# pc_openpressure_basic.net
KiCad netlist of a schematic drawn in EAGLE
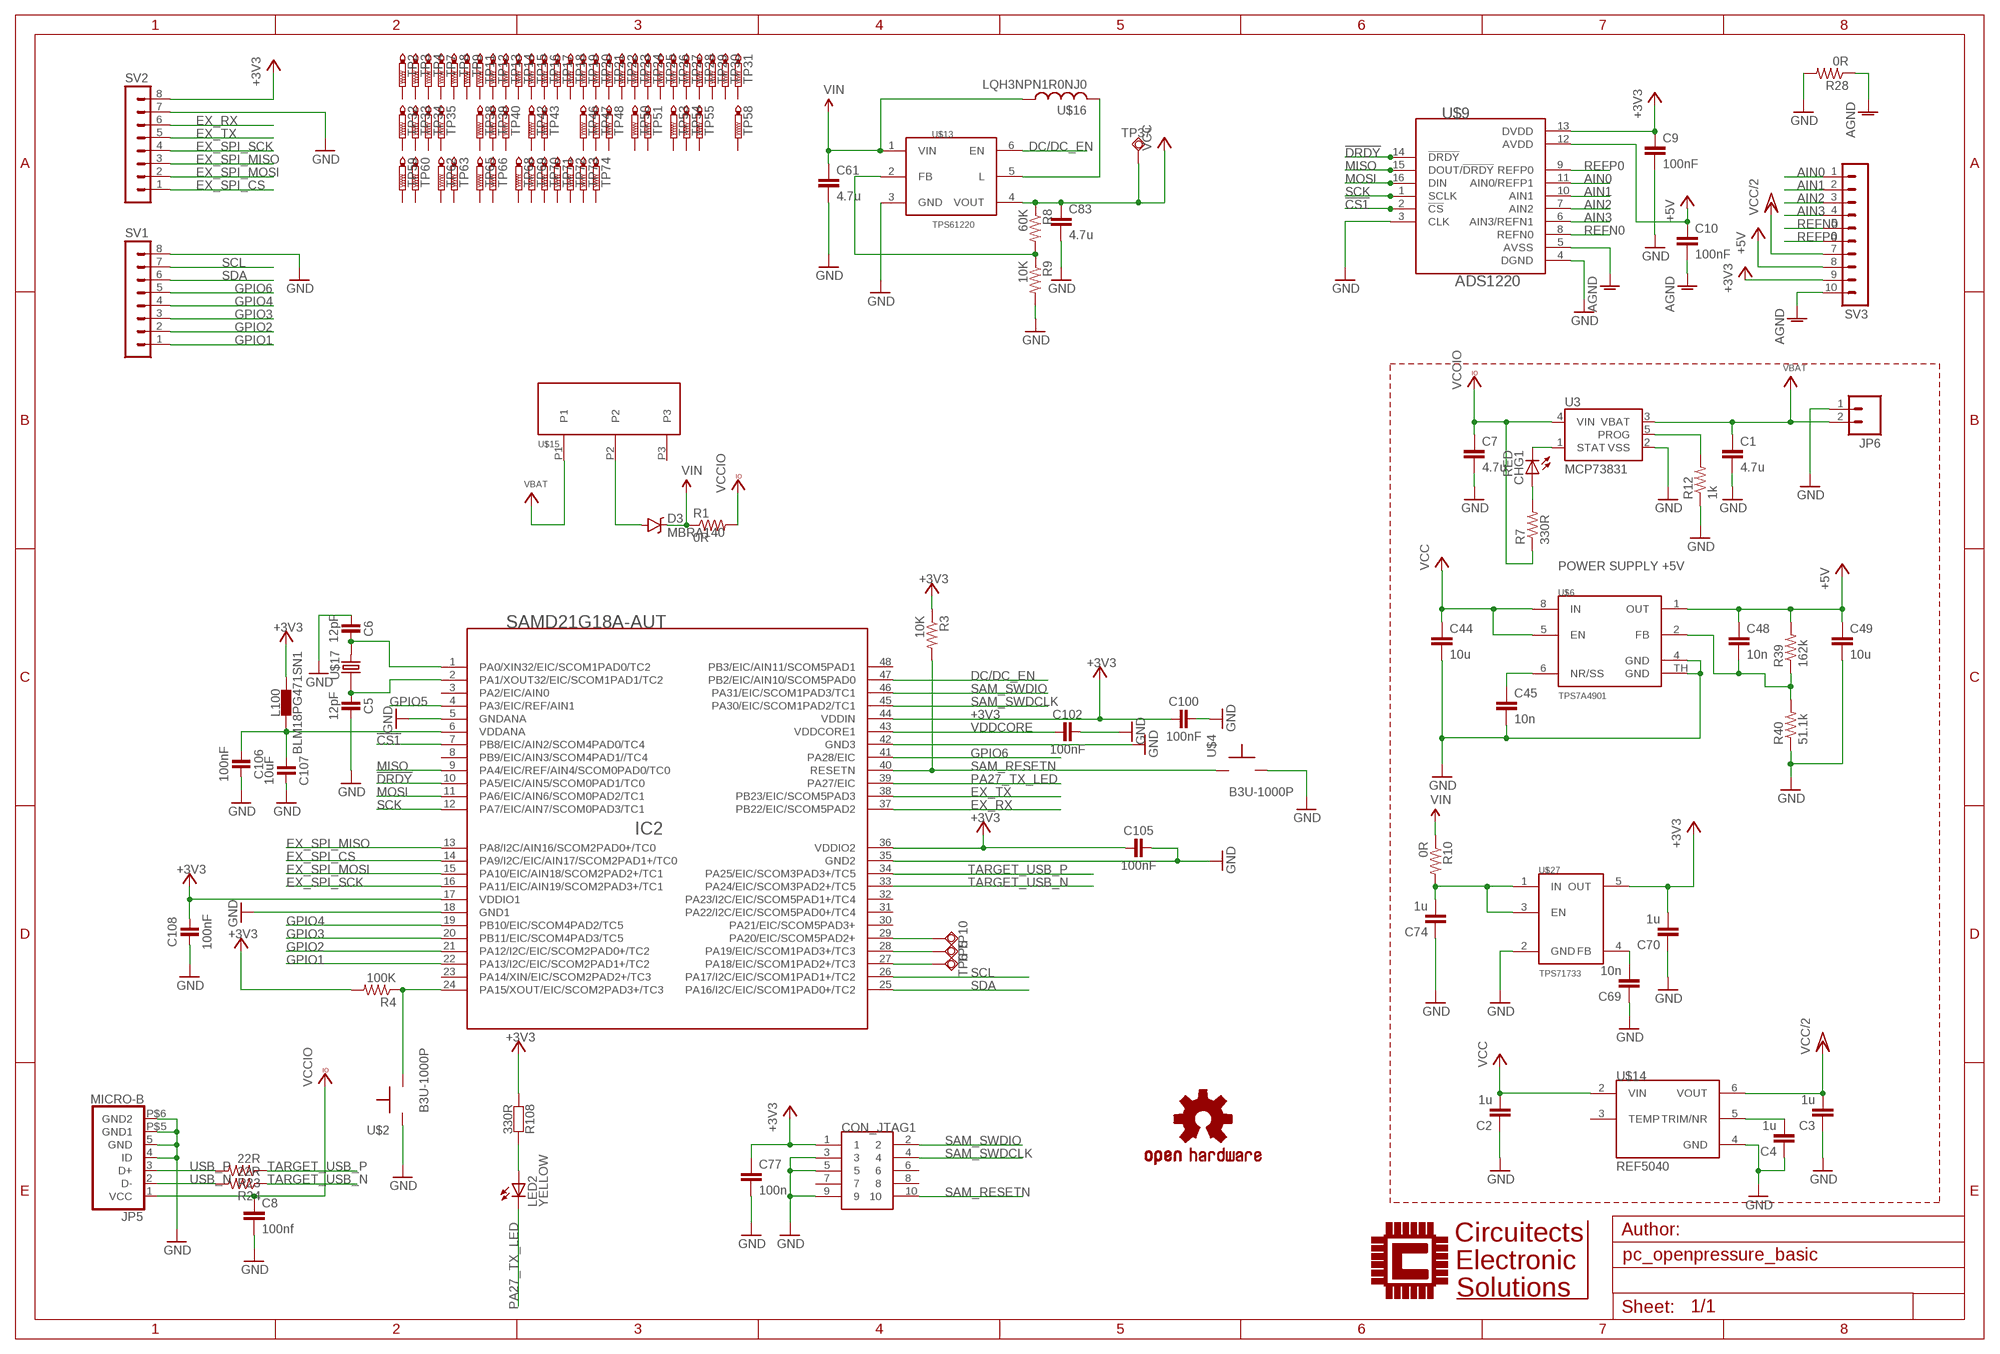
[diagram p0: schematic, sheet 1]

(export (version "E")
  (design (tool "Eeschema 10.0.6"))
  (components
    (comp (ref "C1")
      (value "4.7u")
      (footprint "eagle-import:C0805")
      (libsource (lib "eagle-import") (part "C-EUC0805"))
    )
    (comp (ref "C2")
      (value "1u")
      (footprint "eagle-import:C0805")
      (libsource (lib "eagle-import") (part "C-EUC0805"))
    )
    (comp (ref "C3")
      (value "1u")
      (footprint "eagle-import:C0805")
      (libsource (lib "eagle-import") (part "C-EUC0805"))
    )
    (comp (ref "C4")
      (value "1u")
      (footprint "eagle-import:C0805")
      (libsource (lib "eagle-import") (part "C-EUC0805"))
    )
    (comp (ref "C5")
      (value "12pF")
      (footprint "eagle-import:C0402")
      (libsource (lib "eagle-import") (part "CAPACITORS-0402"))
    )
    (comp (ref "C6")
      (value "12pF")
      (footprint "eagle-import:C0402")
      (libsource (lib "eagle-import") (part "CAPACITORS-0402"))
    )
    (comp (ref "C7")
      (value "4.7u")
      (footprint "eagle-import:C0805")
      (libsource (lib "eagle-import") (part "C-EUC0805"))
    )
    (comp (ref "C8")
      (value "100nf")
      (footprint "eagle-import:C0805")
      (libsource (lib "eagle-import") (part "C-EUC0805"))
    )
    (comp (ref "C9")
      (value "100nF")
      (footprint "eagle-import:C0805")
      (libsource (lib "eagle-import") (part "C-EUC0805"))
    )
    (comp (ref "C10")
      (value "100nF")
      (footprint "eagle-import:C0805")
      (libsource (lib "eagle-import") (part "C-EUC0805"))
    )
    (comp (ref "C44")
      (value "10u")
      (footprint "eagle-import:C0805")
      (libsource (lib "eagle-import") (part "C-EUC0805"))
    )
    (comp (ref "C45")
      (value "10n")
      (footprint "eagle-import:C0402")
      (libsource (lib "eagle-import") (part "C-EUC0402"))
    )
    (comp (ref "C48")
      (value "10n")
      (footprint "eagle-import:C0402")
      (libsource (lib "eagle-import") (part "C-EUC0402"))
    )
    (comp (ref "C49")
      (value "10u")
      (footprint "eagle-import:C0805")
      (libsource (lib "eagle-import") (part "C-EUC0805"))
    )
    (comp (ref "C61")
      (value "4.7u")
      (footprint "eagle-import:C0805")
      (libsource (lib "eagle-import") (part "C-EUC0805"))
    )
    (comp (ref "C69")
      (value "10n")
      (footprint "eagle-import:C0402")
      (libsource (lib "eagle-import") (part "C-EUC0402"))
    )
    (comp (ref "C70")
      (value "1u")
      (footprint "eagle-import:C0805")
      (libsource (lib "eagle-import") (part "C-EUC0805"))
    )
    (comp (ref "C74")
      (value "1u")
      (footprint "eagle-import:C0805")
      (libsource (lib "eagle-import") (part "C-EUC0805"))
    )
    (comp (ref "C77")
      (value "100n")
      (footprint "eagle-import:C0805")
      (libsource (lib "eagle-import") (part "C-EUC0805"))
    )
    (comp (ref "C83")
      (value "4.7u")
      (footprint "eagle-import:C0805")
      (libsource (lib "eagle-import") (part "C-EUC0805"))
    )
    (comp (ref "C100")
      (value "100nF")
      (footprint "eagle-import:C0805")
      (libsource (lib "eagle-import") (part "CAPACITORS-0805"))
    )
    (comp (ref "C102")
      (value "100nF")
      (footprint "eagle-import:C0805")
      (libsource (lib "eagle-import") (part "CAPACITORS-0805"))
    )
    (comp (ref "C105")
      (value "100nF")
      (footprint "eagle-import:C0805")
      (libsource (lib "eagle-import") (part "CAPACITORS-0805"))
    )
    (comp (ref "C106")
      (value "100nF")
      (footprint "eagle-import:C0805")
      (libsource (lib "eagle-import") (part "CAPACITORS-0805"))
    )
    (comp (ref "C107")
      (value "10uF")
      (footprint "eagle-import:C0805")
      (libsource (lib "eagle-import") (part "CAPACITORS-0805"))
    )
    (comp (ref "C108")
      (value "100nF")
      (footprint "eagle-import:C0805")
      (libsource (lib "eagle-import") (part "CAPACITORS-0805"))
    )
    (comp (ref "CHG1")
      (value "RED")
      (footprint "eagle-import:CHIPLED_0603")
      (libsource (lib "eagle-import") (part "LEDCHIPLED_0603"))
    )
    (comp (ref "CON_JTAG1")
      (value "HDR-SMT-50MIL/5X2")
      (footprint "eagle-import:HDR-SMT-50MIL_5X2")
      (libsource (lib "eagle-import") (part "HDR-SMT-50MIL/5X2"))
    )
    (comp (ref "D3")
      (value "MBRA140")
      (footprint "eagle-import:SMA-DIODE")
      (libsource (lib "eagle-import") (part "DIODE-SCHOTTKY-MBRA140"))
    )
    (comp (ref "IC2")
      (value "SAMD21G18A-AUT")
      (footprint "eagle-import:TQFP48")
      (libsource (lib "eagle-import") (part "SAMD21G18A"))
    )
    (comp (ref "JP5")
      (value "MICRO-B")
      (footprint "eagle-import:MICRO-B")
      (libsource (lib "eagle-import") (part "MICRO-B"))
    )
    (comp (ref "JP6")
      (value "M02-JST-2MM-SMT")
      (footprint "eagle-import:JST-2-SMD")
      (libsource (lib "eagle-import") (part "M02-JST-2MM-SMT"))
    )
    (comp (ref "L100")
      (value "BLM18PG471SN1")
      (footprint "eagle-import:C0603")
      (libsource (lib "eagle-import") (part "INDUCTOR-0603"))
    )
    (comp (ref "LED2")
      (value "YELLOW")
      (footprint "eagle-import:CHIPLED_0603")
      (libsource (lib "eagle-import") (part "LEDCHIPLED_0603"))
    )
    (comp (ref "R1")
      (value "0R")
      (footprint "eagle-import:R0402")
      (libsource (lib "eagle-import") (part "R-US_R0402"))
    )
    (comp (ref "R3")
      (value "10K")
      (footprint "eagle-import:R0805")
      (libsource (lib "eagle-import") (part "R-US_R0805"))
    )
    (comp (ref "R4")
      (value "100K")
      (footprint "eagle-import:R0402")
      (libsource (lib "eagle-import") (part "R-US_R0402"))
    )
    (comp (ref "R7")
      (value "330R")
      (footprint "eagle-import:R0805")
      (libsource (lib "eagle-import") (part "R-US_R0805"))
    )
    (comp (ref "R8")
      (value "60K")
      (footprint "eagle-import:R0805")
      (libsource (lib "eagle-import") (part "R-US_R0805"))
    )
    (comp (ref "R9")
      (value "10K")
      (footprint "eagle-import:R0805")
      (libsource (lib "eagle-import") (part "R-US_R0805"))
    )
    (comp (ref "R10")
      (value "0R")
      (footprint "eagle-import:R0402")
      (libsource (lib "eagle-import") (part "R-US_R0402"))
    )
    (comp (ref "R12")
      (value "1k")
      (footprint "eagle-import:R0805")
      (libsource (lib "eagle-import") (part "R-US_R0805"))
    )
    (comp (ref "R23")
      (value "22R")
      (footprint "eagle-import:R0402")
      (libsource (lib "eagle-import") (part "R-US_R0402"))
    )
    (comp (ref "R24")
      (value "22R")
      (footprint "eagle-import:R0402")
      (libsource (lib "eagle-import") (part "R-US_R0402"))
    )
    (comp (ref "R28")
      (value "0R")
      (footprint "eagle-import:R0805")
      (libsource (lib "eagle-import") (part "R-US_R0805"))
    )
    (comp (ref "R39")
      (value "162k")
      (footprint "eagle-import:R0805")
      (libsource (lib "eagle-import") (part "R-US_R0805"))
    )
    (comp (ref "R40")
      (value "51.1k")
      (footprint "eagle-import:R0805")
      (libsource (lib "eagle-import") (part "R-US_R0805"))
    )
    (comp (ref "R108")
      (value "330R")
      (footprint "eagle-import:C0402")
      (libsource (lib "eagle-import") (part "RESISTORS-0402"))
    )
    (comp (ref "SV1")
      (value "MA08-1")
      (footprint "eagle-import:MA08-1")
      (libsource (lib "eagle-import") (part "MA08-1"))
    )
    (comp (ref "SV2")
      (value "MA08-1")
      (footprint "eagle-import:MA08-1")
      (libsource (lib "eagle-import") (part "MA08-1"))
    )
    (comp (ref "SV3")
      (value "MA10-1")
      (footprint "eagle-import:MA10-1")
      (libsource (lib "eagle-import") (part "MA10-1"))
    )
    (comp (ref "TP2")
      (value "PTR1PAD1-13")
      (footprint "eagle-import:P1-13")
      (libsource (lib "eagle-import") (part "PTR1PAD1-13"))
    )
    (comp (ref "TP3")
      (value "PTR1PAD1-13")
      (footprint "eagle-import:P1-13")
      (libsource (lib "eagle-import") (part "PTR1PAD1-13"))
    )
    (comp (ref "TP4")
      (value "PTR1PAD1-13")
      (footprint "eagle-import:P1-13")
      (libsource (lib "eagle-import") (part "PTR1PAD1-13"))
    )
    (comp (ref "TP5")
      (value "TPSQB1,27")
      (footprint "eagle-import:B1,27")
      (libsource (lib "eagle-import") (part "TPSQB1,27"))
    )
    (comp (ref "TP6")
      (value "TPSQB1,27")
      (footprint "eagle-import:B1,27")
      (libsource (lib "eagle-import") (part "TPSQB1,27"))
    )
    (comp (ref "TP7")
      (value "PTR1PAD1-13")
      (footprint "eagle-import:P1-13")
      (libsource (lib "eagle-import") (part "PTR1PAD1-13"))
    )
    (comp (ref "TP8")
      (value "PTR1PAD1-13")
      (footprint "eagle-import:P1-13")
      (libsource (lib "eagle-import") (part "PTR1PAD1-13"))
    )
    (comp (ref "TP9")
      (value "PTR1PAD1-13")
      (footprint "eagle-import:P1-13")
      (libsource (lib "eagle-import") (part "PTR1PAD1-13"))
    )
    (comp (ref "TP10")
      (value "TPSQB1,27")
      (footprint "eagle-import:B1,27")
      (libsource (lib "eagle-import") (part "TPSQB1,27"))
    )
    (comp (ref "TP11")
      (value "PTR1PAD1-13")
      (footprint "eagle-import:P1-13")
      (libsource (lib "eagle-import") (part "PTR1PAD1-13"))
    )
    (comp (ref "TP12")
      (value "PTR1PAD1-13")
      (footprint "eagle-import:P1-13")
      (libsource (lib "eagle-import") (part "PTR1PAD1-13"))
    )
    (comp (ref "TP13")
      (value "PTR1PAD1-13")
      (footprint "eagle-import:P1-13")
      (libsource (lib "eagle-import") (part "PTR1PAD1-13"))
    )
    (comp (ref "TP14")
      (value "PTR1PAD1-13")
      (footprint "eagle-import:P1-13")
      (libsource (lib "eagle-import") (part "PTR1PAD1-13"))
    )
    (comp (ref "TP15")
      (value "PTR1PAD1-13")
      (footprint "eagle-import:P1-13")
      (libsource (lib "eagle-import") (part "PTR1PAD1-13"))
    )
    (comp (ref "TP16")
      (value "PTR1PAD1-13")
      (footprint "eagle-import:P1-13")
      (libsource (lib "eagle-import") (part "PTR1PAD1-13"))
    )
    (comp (ref "TP17")
      (value "PTR1PAD1-13")
      (footprint "eagle-import:P1-13")
      (libsource (lib "eagle-import") (part "PTR1PAD1-13"))
    )
    (comp (ref "TP18")
      (value "PTR1PAD1-13")
      (footprint "eagle-import:P1-13")
      (libsource (lib "eagle-import") (part "PTR1PAD1-13"))
    )
    (comp (ref "TP19")
      (value "PTR1PAD1-13")
      (footprint "eagle-import:P1-13")
      (libsource (lib "eagle-import") (part "PTR1PAD1-13"))
    )
    (comp (ref "TP20")
      (value "PTR1PAD1-13")
      (footprint "eagle-import:P1-13")
      (libsource (lib "eagle-import") (part "PTR1PAD1-13"))
    )
    (comp (ref "TP21")
      (value "PTR1PAD1-13")
      (footprint "eagle-import:P1-13")
      (libsource (lib "eagle-import") (part "PTR1PAD1-13"))
    )
    (comp (ref "TP22")
      (value "PTR1PAD1-13")
      (footprint "eagle-import:P1-13")
      (libsource (lib "eagle-import") (part "PTR1PAD1-13"))
    )
    (comp (ref "TP23")
      (value "PTR1PAD1-13")
      (footprint "eagle-import:P1-13")
      (libsource (lib "eagle-import") (part "PTR1PAD1-13"))
    )
    (comp (ref "TP24")
      (value "PTR1PAD1-13")
      (footprint "eagle-import:P1-13")
      (libsource (lib "eagle-import") (part "PTR1PAD1-13"))
    )
    (comp (ref "TP25")
      (value "PTR1PAD1-13")
      (footprint "eagle-import:P1-13")
      (libsource (lib "eagle-import") (part "PTR1PAD1-13"))
    )
    (comp (ref "TP26")
      (value "PTR1PAD1-13")
      (footprint "eagle-import:P1-13")
      (libsource (lib "eagle-import") (part "PTR1PAD1-13"))
    )
    (comp (ref "TP27")
      (value "PTR1PAD1-13")
      (footprint "eagle-import:P1-13")
      (libsource (lib "eagle-import") (part "PTR1PAD1-13"))
    )
    (comp (ref "TP28")
      (value "PTR1PAD1-13")
      (footprint "eagle-import:P1-13")
      (libsource (lib "eagle-import") (part "PTR1PAD1-13"))
    )
    (comp (ref "TP29")
      (value "PTR1PAD1-13")
      (footprint "eagle-import:P1-13")
      (libsource (lib "eagle-import") (part "PTR1PAD1-13"))
    )
    (comp (ref "TP30")
      (value "PTR1PAD1-13")
      (footprint "eagle-import:P1-13")
      (libsource (lib "eagle-import") (part "PTR1PAD1-13"))
    )
    (comp (ref "TP31")
      (value "PTR1PAD1-13")
      (footprint "eagle-import:P1-13")
      (libsource (lib "eagle-import") (part "PTR1PAD1-13"))
    )
    (comp (ref "TP32")
      (value "PTR1PAD1-13")
      (footprint "eagle-import:P1-13")
      (libsource (lib "eagle-import") (part "PTR1PAD1-13"))
    )
    (comp (ref "TP33")
      (value "PTR1PAD1-13")
      (footprint "eagle-import:P1-13")
      (libsource (lib "eagle-import") (part "PTR1PAD1-13"))
    )
    (comp (ref "TP34")
      (value "PTR1PAD1-13")
      (footprint "eagle-import:P1-13")
      (libsource (lib "eagle-import") (part "PTR1PAD1-13"))
    )
    (comp (ref "TP35")
      (value "PTR1PAD1-13")
      (footprint "eagle-import:P1-13")
      (libsource (lib "eagle-import") (part "PTR1PAD1-13"))
    )
    (comp (ref "TP37")
      (value "TPSQB1,27")
      (footprint "eagle-import:B1,27")
      (libsource (lib "eagle-import") (part "TPSQB1,27"))
    )
    (comp (ref "TP38")
      (value "PTR1PAD1-13")
      (footprint "eagle-import:P1-13")
      (libsource (lib "eagle-import") (part "PTR1PAD1-13"))
    )
    (comp (ref "TP39")
      (value "PTR1PAD1-13")
      (footprint "eagle-import:P1-13")
      (libsource (lib "eagle-import") (part "PTR1PAD1-13"))
    )
    (comp (ref "TP40")
      (value "PTR1PAD1-13")
      (footprint "eagle-import:P1-13")
      (libsource (lib "eagle-import") (part "PTR1PAD1-13"))
    )
    (comp (ref "TP42")
      (value "PTR1PAD1-13")
      (footprint "eagle-import:P1-13")
      (libsource (lib "eagle-import") (part "PTR1PAD1-13"))
    )
    (comp (ref "TP43")
      (value "PTR1PAD1-13")
      (footprint "eagle-import:P1-13")
      (libsource (lib "eagle-import") (part "PTR1PAD1-13"))
    )
    (comp (ref "TP46")
      (value "PTR1PAD1-13")
      (footprint "eagle-import:P1-13")
      (libsource (lib "eagle-import") (part "PTR1PAD1-13"))
    )
    (comp (ref "TP47")
      (value "PTR1PAD1-13")
      (footprint "eagle-import:P1-13")
      (libsource (lib "eagle-import") (part "PTR1PAD1-13"))
    )
    (comp (ref "TP48")
      (value "PTR1PAD1-13")
      (footprint "eagle-import:P1-13")
      (libsource (lib "eagle-import") (part "PTR1PAD1-13"))
    )
    (comp (ref "TP50")
      (value "PTR1PAD1-13")
      (footprint "eagle-import:P1-13")
      (libsource (lib "eagle-import") (part "PTR1PAD1-13"))
    )
    (comp (ref "TP51")
      (value "PTR1PAD1-13")
      (footprint "eagle-import:P1-13")
      (libsource (lib "eagle-import") (part "PTR1PAD1-13"))
    )
    (comp (ref "TP53")
      (value "PTR1PAD1-13")
      (footprint "eagle-import:P1-13")
      (libsource (lib "eagle-import") (part "PTR1PAD1-13"))
    )
    (comp (ref "TP54")
      (value "PTR1PAD1-13")
      (footprint "eagle-import:P1-13")
      (libsource (lib "eagle-import") (part "PTR1PAD1-13"))
    )
    (comp (ref "TP55")
      (value "PTR1PAD1-13")
      (footprint "eagle-import:P1-13")
      (libsource (lib "eagle-import") (part "PTR1PAD1-13"))
    )
    (comp (ref "TP58")
      (value "PTR1PAD1-13")
      (footprint "eagle-import:P1-13")
      (libsource (lib "eagle-import") (part "PTR1PAD1-13"))
    )
    (comp (ref "TP59")
      (value "PTR1PAD1-13")
      (footprint "eagle-import:P1-13")
      (libsource (lib "eagle-import") (part "PTR1PAD1-13"))
    )
    (comp (ref "TP60")
      (value "PTR1PAD1-13")
      (footprint "eagle-import:P1-13")
      (libsource (lib "eagle-import") (part "PTR1PAD1-13"))
    )
    (comp (ref "TP62")
      (value "PTR1PAD1-13")
      (footprint "eagle-import:P1-13")
      (libsource (lib "eagle-import") (part "PTR1PAD1-13"))
    )
    (comp (ref "TP63")
      (value "PTR1PAD1-13")
      (footprint "eagle-import:P1-13")
      (libsource (lib "eagle-import") (part "PTR1PAD1-13"))
    )
    (comp (ref "TP65")
      (value "PTR1PAD1-13")
      (footprint "eagle-import:P1-13")
      (libsource (lib "eagle-import") (part "PTR1PAD1-13"))
    )
    (comp (ref "TP66")
      (value "PTR1PAD1-13")
      (footprint "eagle-import:P1-13")
      (libsource (lib "eagle-import") (part "PTR1PAD1-13"))
    )
    (comp (ref "TP68")
      (value "PTR1PAD1-13")
      (footprint "eagle-import:P1-13")
      (libsource (lib "eagle-import") (part "PTR1PAD1-13"))
    )
    (comp (ref "TP69")
      (value "PTR1PAD1-13")
      (footprint "eagle-import:P1-13")
      (libsource (lib "eagle-import") (part "PTR1PAD1-13"))
    )
    (comp (ref "TP70")
      (value "PTR1PAD1-13")
      (footprint "eagle-import:P1-13")
      (libsource (lib "eagle-import") (part "PTR1PAD1-13"))
    )
    (comp (ref "TP71")
      (value "PTR1PAD1-13")
      (footprint "eagle-import:P1-13")
      (libsource (lib "eagle-import") (part "PTR1PAD1-13"))
    )
    (comp (ref "TP72")
      (value "PTR1PAD1-13")
      (footprint "eagle-import:P1-13")
      (libsource (lib "eagle-import") (part "PTR1PAD1-13"))
    )
    (comp (ref "TP73")
      (value "PTR1PAD1-13")
      (footprint "eagle-import:P1-13")
      (libsource (lib "eagle-import") (part "PTR1PAD1-13"))
    )
    (comp (ref "TP74")
      (value "PTR1PAD1-13")
      (footprint "eagle-import:P1-13")
      (libsource (lib "eagle-import") (part "PTR1PAD1-13"))
    )
    (comp (ref "U$2")
      (value "B3U-1000P")
      (footprint "eagle-import:B3U-1000P")
      (libsource (lib "eagle-import") (part "B3U-1000P"))
    )
    (comp (ref "U$4")
      (value "B3U-1000P")
      (footprint "eagle-import:B3U-1000P")
      (libsource (lib "eagle-import") (part "B3U-1000P"))
    )
    (comp (ref "U$6")
      (value "TPS7A4901")
      (footprint "eagle-import:S-PDSO-G08")
      (libsource (lib "eagle-import") (part "TPS7A4901"))
    )
    (comp (ref "U$7")
      (value "CES-LOGO")
      (footprint "eagle-import:CES-LOGO-SMALL")
      (libsource (lib "eagle-import") (part "CES-LOGO"))
    )
    (comp (ref "U$8")
      (value "PROTY-LOGO")
      (footprint "eagle-import:LOGO-PROTY")
      (libsource (lib "eagle-import") (part "PROTY-LOGO"))
    )
    (comp (ref "U$9")
      (value "ADS1220")
      (footprint "eagle-import:TSSOP-16")
      (libsource (lib "eagle-import") (part "ADS1220"))
    )
    (comp (ref "U$13")
      (value "TPS61220")
      (footprint "eagle-import:SC-70-6")
      (libsource (lib "eagle-import") (part "TPS61222"))
    )
    (comp (ref "U$14")
      (value "REF5040")
      (footprint "eagle-import:SO-08M")
      (libsource (lib "eagle-import") (part "REF5040"))
    )
    (comp (ref "U$15")
      (value "PCM12SMTR")
      (footprint "eagle-import:PCM12SMTR")
      (libsource (lib "eagle-import") (part "PCM12SMTR"))
    )
    (comp (ref "U$16")
      (value "LQH3NPN1R0NJ0")
      (footprint "eagle-import:LQH3NP")
      (libsource (lib "eagle-import") (part "LQH3NPN1R0NJ0"))
    )
    (comp (ref "U$17")
      (value "ECS-X-34B")
      (footprint "eagle-import:ECX-31B")
      (libsource (lib "eagle-import") (part "ECS-X-34B"))
    )
    (comp (ref "U$18")
      (value "PROTY_LOGO_WITH_TEXT")
      (footprint "eagle-import:PROTY_WITH_TEXT")
      (libsource (lib "eagle-import") (part "PROTY_LOGO_WITH_TEXT"))
    )
    (comp (ref "U$19")
      (value "OSHW-LOGOM")
      (footprint "eagle-import:OSHW-LOGO-M")
      (libsource (lib "eagle-import") (part "OSHW-LOGOM"))
    )
    (comp (ref "U$27")
      (value "TPS71733")
      (footprint "eagle-import:SC70-5")
      (libsource (lib "eagle-import") (part "TPS717XX"))
    )
    (comp (ref "U3")
      (value "MCP73831")
      (footprint "eagle-import:SOT23-5")
      (libsource (lib "eagle-import") (part "MCP73831"))
    )
  )
  (nets
    (net (code "1") (name "+3V3") (class "Default")
      (node (ref "C100") (pin "1") (pinfunction "1_1") (pintype "passive"))
      (node (ref "C105") (pin "1") (pinfunction "1_1") (pintype "passive"))
      (node (ref "C108") (pin "2") (pinfunction "2_2") (pintype "passive"))
      (node (ref "C70") (pin "2") (pinfunction "2_2") (pintype "passive"))
      (node (ref "C77") (pin "1") (pinfunction "1_1") (pintype "passive"))
      (node (ref "C9") (pin "1") (pinfunction "1_1") (pintype "passive"))
      (node (ref "CON_JTAG1") (pin "1") (pinfunction "1_1") (pintype "bidirectional"))
      (node (ref "IC2") (pin "17") (pinfunction "VDDIO1_17") (pintype "power_in"))
      (node (ref "IC2") (pin "36") (pinfunction "VDDIO2_36") (pintype "power_in"))
      (node (ref "IC2") (pin "44") (pinfunction "VDDIN_44") (pintype "power_in"))
      (node (ref "L100") (pin "2") (pinfunction "2_2") (pintype "passive"))
      (node (ref "R108") (pin "1") (pinfunction "1_1") (pintype "passive"))
      (node (ref "R3") (pin "1") (pinfunction "1_1") (pintype "passive"))
      (node (ref "R4") (pin "2") (pinfunction "2_2") (pintype "passive"))
      (node (ref "SV2") (pin "8") (pinfunction "8_8") (pintype "passive"))
      (node (ref "SV3") (pin "9") (pinfunction "9_9") (pintype "passive"))
      (node (ref "U$27") (pin "5") (pinfunction "OUT_5") (pintype "bidirectional"))
      (node (ref "U$9") (pin "13") (pinfunction "DVDD_13") (pintype "bidirectional"))
    )
    (net (code "2") (name "+5V") (class "Default")
      (node (ref "C10") (pin "1") (pinfunction "1_1") (pintype "passive"))
      (node (ref "C48") (pin "1") (pinfunction "1_1") (pintype "passive"))
      (node (ref "C49") (pin "1") (pinfunction "1_1") (pintype "passive"))
      (node (ref "R39") (pin "2") (pinfunction "2_2") (pintype "passive"))
      (node (ref "SV3") (pin "8") (pinfunction "8_8") (pintype "passive"))
      (node (ref "U$6") (pin "1") (pinfunction "OUT_1") (pintype "bidirectional"))
      (node (ref "U$9") (pin "12") (pinfunction "AVDD_12") (pintype "bidirectional"))
    )
    (net (code "3") (name "/AIN0") (class "Default")
      (node (ref "SV3") (pin "1") (pinfunction "1_1") (pintype "passive"))
      (node (ref "U$9") (pin "11") (pinfunction "AIN0/REFP1_11") (pintype "bidirectional"))
    )
    (net (code "4") (name "/AIN1") (class "Default")
      (node (ref "SV3") (pin "2") (pinfunction "2_2") (pintype "passive"))
      (node (ref "U$9") (pin "10") (pinfunction "AIN1_10") (pintype "bidirectional"))
    )
    (net (code "5") (name "/AIN2") (class "Default")
      (node (ref "SV3") (pin "3") (pinfunction "3_3") (pintype "passive"))
      (node (ref "U$9") (pin "7") (pinfunction "AIN2_7") (pintype "bidirectional"))
    )
    (net (code "6") (name "/AIN3") (class "Default")
      (node (ref "SV3") (pin "4") (pinfunction "4_4") (pintype "passive"))
      (node (ref "U$9") (pin "6") (pinfunction "AIN3/REFN1_6") (pintype "bidirectional"))
    )
    (net (code "7") (name "/DC{slash}DC_EN") (class "Default")
      (node (ref "IC2") (pin "47") (pinfunction "PB2/EIC/AIN10/SCOM5PAD0_47") (pintype "bidirectional"))
      (node (ref "U$13") (pin "6") (pinfunction "EN_6") (pintype "bidirectional"))
    )
    (net (code "8") (name "/EX_RX") (class "Default")
      (node (ref "IC2") (pin "37") (pinfunction "PB22/EIC/SCOM5PAD2_37") (pintype "bidirectional"))
      (node (ref "SV2") (pin "6") (pinfunction "6_6") (pintype "passive"))
    )
    (net (code "9") (name "/EX_SPI_CS") (class "Default")
      (node (ref "IC2") (pin "14") (pinfunction "PA9/I2C/EIC/AIN17/SCOM2PAD1+/TC0_14") (pintype "bidirectional"))
      (node (ref "SV2") (pin "1") (pinfunction "1_1") (pintype "passive"))
    )
    (net (code "10") (name "/EX_SPI_MISO") (class "Default")
      (node (ref "IC2") (pin "13") (pinfunction "PA8/I2C/AIN16/SCOM2PAD0+/TC0_13") (pintype "bidirectional"))
      (node (ref "SV2") (pin "3") (pinfunction "3_3") (pintype "passive"))
    )
    (net (code "11") (name "/EX_SPI_MOSI") (class "Default")
      (node (ref "IC2") (pin "15") (pinfunction "PA10/EIC/AIN18/SCOM2PAD2+/TC1_15") (pintype "bidirectional"))
      (node (ref "SV2") (pin "2") (pinfunction "2_2") (pintype "passive"))
    )
    (net (code "12") (name "/EX_SPI_SCK") (class "Default")
      (node (ref "IC2") (pin "16") (pinfunction "PA11/EIC/AIN19/SCOM2PAD3+/TC1_16") (pintype "bidirectional"))
      (node (ref "SV2") (pin "4") (pinfunction "4_4") (pintype "passive"))
    )
    (net (code "13") (name "/EX_TX") (class "Default")
      (node (ref "IC2") (pin "38") (pinfunction "PB23/EIC/SCOM5PAD3_38") (pintype "bidirectional"))
      (node (ref "SV2") (pin "5") (pinfunction "5_5") (pintype "passive"))
    )
    (net (code "14") (name "/GPIO1") (class "Default")
      (node (ref "IC2") (pin "22") (pinfunction "PA13/I2C/EIC/SCOM2PAD1+/TC2_22") (pintype "bidirectional"))
      (node (ref "SV1") (pin "1") (pinfunction "1_1") (pintype "passive"))
    )
    (net (code "15") (name "/GPIO2") (class "Default")
      (node (ref "IC2") (pin "21") (pinfunction "PA12/I2C/EIC/SCOM2PAD0+/TC2_21") (pintype "bidirectional"))
      (node (ref "SV1") (pin "2") (pinfunction "2_2") (pintype "passive"))
    )
    (net (code "16") (name "/GPIO3") (class "Default")
      (node (ref "IC2") (pin "20") (pinfunction "PB11/EIC/SCOM4PAD3/TC5_20") (pintype "bidirectional"))
      (node (ref "SV1") (pin "3") (pinfunction "3_3") (pintype "passive"))
    )
    (net (code "17") (name "/GPIO4") (class "Default")
      (node (ref "IC2") (pin "19") (pinfunction "PB10/EIC/SCOM4PAD2/TC5_19") (pintype "bidirectional"))
      (node (ref "SV1") (pin "4") (pinfunction "4_4") (pintype "passive"))
    )
    (net (code "18") (name "/GPIO5") (class "Default")
      (node (ref "IC2") (pin "4") (pinfunction "PA3/EIC/REF/AIN1_4") (pintype "bidirectional"))
    )
    (net (code "19") (name "/GPIO6") (class "Default")
      (node (ref "IC2") (pin "41") (pinfunction "PA28/EIC_41") (pintype "bidirectional"))
      (node (ref "SV1") (pin "5") (pinfunction "5_5") (pintype "passive"))
    )
    (net (code "20") (name "/MISO") (class "Default")
      (node (ref "IC2") (pin "9") (pinfunction "PA4/EIC/REF/AIN4/SCOM0PAD0/TC0_9") (pintype "bidirectional"))
      (node (ref "U$9") (pin "15") (pinfunction "DOUT/~{DRDY}_15") (pintype "bidirectional"))
    )
    (net (code "21") (name "/MOSI") (class "Default")
      (node (ref "IC2") (pin "11") (pinfunction "PA6/EIC/AIN6/SCOM0PAD2/TC1_11") (pintype "bidirectional"))
      (node (ref "U$9") (pin "16") (pinfunction "DIN_16") (pintype "bidirectional"))
    )
    (net (code "22") (name "/PA27_TX_LED") (class "Default")
      (node (ref "IC2") (pin "39") (pinfunction "PA27/EIC_39") (pintype "bidirectional"))
      (node (ref "LED2") (pin "C") (pinfunction "C_C") (pintype "passive"))
    )
    (net (code "23") (name "/REFN0") (class "Default")
      (node (ref "SV3") (pin "5") (pinfunction "5_5") (pintype "passive"))
      (node (ref "U$9") (pin "8") (pinfunction "REFN0_8") (pintype "bidirectional"))
    )
    (net (code "24") (name "/REFP0") (class "Default")
      (node (ref "SV3") (pin "6") (pinfunction "6_6") (pintype "passive"))
      (node (ref "U$9") (pin "9") (pinfunction "REFP0_9") (pintype "bidirectional"))
    )
    (net (code "25") (name "/SAM_RESETN") (class "Default")
      (node (ref "CON_JTAG1") (pin "10") (pinfunction "10_10") (pintype "bidirectional"))
      (node (ref "IC2") (pin "40") (pinfunction "RESETN_40") (pintype "bidirectional"))
      (node (ref "R3") (pin "2") (pinfunction "2_2") (pintype "passive"))
      (node (ref "U$4") (pin "P$1") (pinfunction "P$1_P$1") (pintype "bidirectional"))
    )
    (net (code "26") (name "/SAM_SWDCLK") (class "Default")
      (node (ref "CON_JTAG1") (pin "4") (pinfunction "4_4") (pintype "bidirectional"))
      (node (ref "IC2") (pin "45") (pinfunction "PA30/EIC/SCOM1PAD2/TC1_45") (pintype "bidirectional"))
    )
    (net (code "27") (name "/SAM_SWDIO") (class "Default")
      (node (ref "CON_JTAG1") (pin "2") (pinfunction "2_2") (pintype "bidirectional"))
      (node (ref "IC2") (pin "46") (pinfunction "PA31/EIC/SCOM1PAD3/TC1_46") (pintype "bidirectional"))
    )
    (net (code "28") (name "/SCK") (class "Default")
      (node (ref "IC2") (pin "12") (pinfunction "PA7/EIC/AIN7/SCOM0PAD3/TC1_12") (pintype "bidirectional"))
      (node (ref "U$9") (pin "1") (pinfunction "SCLK_1") (pintype "bidirectional"))
    )
    (net (code "29") (name "/SCL") (class "Default")
      (node (ref "IC2") (pin "26") (pinfunction "PA17/I2C/EIC/SCOM1PAD1+/TC2_26") (pintype "bidirectional"))
      (node (ref "SV1") (pin "7") (pinfunction "7_7") (pintype "passive"))
    )
    (net (code "30") (name "/SDA") (class "Default")
      (node (ref "IC2") (pin "25") (pinfunction "PA16/I2C/EIC/SCOM1PAD0+/TC2_25") (pintype "bidirectional"))
      (node (ref "SV1") (pin "6") (pinfunction "6_6") (pintype "passive"))
    )
    (net (code "31") (name "/TARGET_USB_N") (class "Default")
      (node (ref "IC2") (pin "33") (pinfunction "PA24/EIC/SCOM3PAD2+/TC5_33") (pintype "bidirectional"))
      (node (ref "R24") (pin "1") (pinfunction "1_1") (pintype "passive"))
    )
    (net (code "32") (name "/TARGET_USB_P") (class "Default")
      (node (ref "IC2") (pin "34") (pinfunction "PA25/EIC/SCOM3PAD3+/TC5_34") (pintype "bidirectional"))
      (node (ref "R23") (pin "1") (pinfunction "1_1") (pintype "passive"))
    )
    (net (code "33") (name "/USB_N") (class "Default")
      (node (ref "JP5") (pin "2") (pinfunction "D-_2") (pintype "bidirectional"))
      (node (ref "R24") (pin "2") (pinfunction "2_2") (pintype "passive"))
    )
    (net (code "34") (name "/USB_P") (class "Default")
      (node (ref "JP5") (pin "3") (pinfunction "D+_3") (pintype "bidirectional"))
      (node (ref "R23") (pin "2") (pinfunction "2_2") (pintype "passive"))
    )
    (net (code "35") (name "/VDDCORE") (class "Default")
      (node (ref "C102") (pin "1") (pinfunction "1_1") (pintype "passive"))
      (node (ref "IC2") (pin "43") (pinfunction "VDDCORE1_43") (pintype "input"))
    )
    (net (code "36") (name "/~{CS1}") (class "Default")
      (node (ref "IC2") (pin "7") (pinfunction "PB8/EIC/AIN2/SCOM4PAD0/TC4_7") (pintype "bidirectional"))
      (node (ref "U$9") (pin "2") (pinfunction "~{CS}_2") (pintype "bidirectional"))
    )
    (net (code "37") (name "/~{DRDY}") (class "Default")
      (node (ref "IC2") (pin "10") (pinfunction "PA5/EIC/AIN5/SCOM0PAD1/TC0_10") (pintype "bidirectional"))
      (node (ref "U$9") (pin "14") (pinfunction "~{DRDY}_14") (pintype "bidirectional"))
    )
    (net (code "38") (name "AGND") (class "Default")
      (node (ref "C10") (pin "2") (pinfunction "2_2") (pintype "passive"))
      (node (ref "R28") (pin "1") (pinfunction "1_1") (pintype "passive"))
      (node (ref "SV3") (pin "10") (pinfunction "10_10") (pintype "passive"))
      (node (ref "U$9") (pin "5") (pinfunction "AVSS_5") (pintype "bidirectional"))
    )
    (net (code "39") (name "GND") (class "Default")
      (node (ref "C1") (pin "2") (pinfunction "2_2") (pintype "passive"))
      (node (ref "C100") (pin "2") (pinfunction "2_2") (pintype "passive"))
      (node (ref "C102") (pin "2") (pinfunction "2_2") (pintype "passive"))
      (node (ref "C105") (pin "2") (pinfunction "2_2") (pintype "passive"))
      (node (ref "C106") (pin "2") (pinfunction "2_2") (pintype "passive"))
      (node (ref "C107") (pin "2") (pinfunction "2_2") (pintype "passive"))
      (node (ref "C108") (pin "1") (pinfunction "1_1") (pintype "passive"))
      (node (ref "C2") (pin "1") (pinfunction "1_1") (pintype "passive"))
      (node (ref "C3") (pin "1") (pinfunction "1_1") (pintype "passive"))
      (node (ref "C4") (pin "1") (pinfunction "1_1") (pintype "passive"))
      (node (ref "C44") (pin "2") (pinfunction "2_2") (pintype "passive"))
      (node (ref "C45") (pin "2") (pinfunction "2_2") (pintype "passive"))
      (node (ref "C49") (pin "2") (pinfunction "2_2") (pintype "passive"))
      (node (ref "C5") (pin "2") (pinfunction "2_2") (pintype "passive"))
      (node (ref "C6") (pin "1") (pinfunction "1_1") (pintype "passive"))
      (node (ref "C61") (pin "2") (pinfunction "2_2") (pintype "passive"))
      (node (ref "C69") (pin "1") (pinfunction "1_1") (pintype "passive"))
      (node (ref "C7") (pin "2") (pinfunction "2_2") (pintype "passive"))
      (node (ref "C70") (pin "1") (pinfunction "1_1") (pintype "passive"))
      (node (ref "C74") (pin "1") (pinfunction "1_1") (pintype "passive"))
      (node (ref "C77") (pin "2") (pinfunction "2_2") (pintype "passive"))
      (node (ref "C8") (pin "2") (pinfunction "2_2") (pintype "passive"))
      (node (ref "C83") (pin "2") (pinfunction "2_2") (pintype "passive"))
      (node (ref "C9") (pin "2") (pinfunction "2_2") (pintype "passive"))
      (node (ref "CON_JTAG1") (pin "3") (pinfunction "3_3") (pintype "bidirectional"))
      (node (ref "CON_JTAG1") (pin "5") (pinfunction "5_5") (pintype "bidirectional"))
      (node (ref "CON_JTAG1") (pin "9") (pinfunction "9_9") (pintype "bidirectional"))
      (node (ref "IC2") (pin "18") (pinfunction "GND1_18") (pintype "power_in"))
      (node (ref "IC2") (pin "35") (pinfunction "GND2_35") (pintype "power_in"))
      (node (ref "IC2") (pin "42") (pinfunction "GND3_42") (pintype "power_in"))
      (node (ref "IC2") (pin "5") (pinfunction "GNDANA_5") (pintype "power_in"))
      (node (ref "JP5") (pin "4") (pinfunction "ID_4") (pintype "bidirectional"))
      (node (ref "JP5") (pin "5") (pinfunction "GND_5") (pintype "bidirectional"))
      (node (ref "JP5") (pin "P$5") (pinfunction "GND1_P$5") (pintype "bidirectional"))
      (node (ref "JP5") (pin "P$6") (pinfunction "GND2_P$6") (pintype "bidirectional"))
      (node (ref "JP6") (pin "1") (pinfunction "1_1") (pintype "passive"))
      (node (ref "R12") (pin "1") (pinfunction "1_1") (pintype "passive"))
      (node (ref "R28") (pin "2") (pinfunction "2_2") (pintype "passive"))
      (node (ref "R40") (pin "1") (pinfunction "1_1") (pintype "passive"))
      (node (ref "R9") (pin "2") (pinfunction "2_2") (pintype "passive"))
      (node (ref "SV1") (pin "8") (pinfunction "8_8") (pintype "passive"))
      (node (ref "SV2") (pin "7") (pinfunction "7_7") (pintype "passive"))
      (node (ref "U$13") (pin "3") (pinfunction "GND_3") (pintype "bidirectional"))
      (node (ref "U$14") (pin "4") (pinfunction "GND_4") (pintype "bidirectional"))
      (node (ref "U$2") (pin "P$1") (pinfunction "P$1_P$1") (pintype "bidirectional"))
      (node (ref "U$27") (pin "2") (pinfunction "GND_2") (pintype "bidirectional"))
      (node (ref "U$4") (pin "P$2") (pinfunction "P$2_P$2") (pintype "bidirectional"))
      (node (ref "U$6") (pin "4") (pinfunction "GND_4") (pintype "bidirectional"))
      (node (ref "U$6") (pin "TH") (pinfunction "GND_TH") (pintype "bidirectional"))
      (node (ref "U$9") (pin "3") (pinfunction "CLK_3") (pintype "bidirectional"))
      (node (ref "U$9") (pin "4") (pinfunction "DGND_4") (pintype "bidirectional"))
      (node (ref "U3") (pin "2") (pinfunction "VSS_2") (pintype "power_in"))
    )
    (net (code "40") (name "Net-(CHG1-PadA)") (class "Default")
      (node (ref "CHG1") (pin "A") (pinfunction "A_A") (pintype "passive"))
      (node (ref "R7") (pin "2") (pinfunction "2_2") (pintype "passive"))
    )
    (net (code "41") (name "Net-(D3-PadA)") (class "Default")
      (node (ref "D3") (pin "A") (pinfunction "A_A") (pintype "passive"))
      (node (ref "U$15") (pin "P2") (pinfunction "P2_P2") (pintype "bidirectional"))
    )
    (net (code "42") (name "Net-(IC2-PA0{slash}XIN32{slash}EIC{slash}SCOM1PAD0{slash}TC2)") (class "Default")
      (node (ref "C6") (pin "2") (pinfunction "2_2") (pintype "passive"))
      (node (ref "IC2") (pin "1") (pinfunction "PA0/XIN32/EIC/SCOM1PAD0/TC2_1") (pintype "bidirectional"))
      (node (ref "U$17") (pin "P$2") (pinfunction "2_P$2") (pintype "passive"))
    )
    (net (code "43") (name "Net-(IC2-PA1{slash}XOUT32{slash}EIC{slash}SCOM1PAD1{slash}TC2)") (class "Default")
      (node (ref "C5") (pin "1") (pinfunction "1_1") (pintype "passive"))
      (node (ref "IC2") (pin "2") (pinfunction "PA1/XOUT32/EIC/SCOM1PAD1/TC2_2") (pintype "bidirectional"))
      (node (ref "U$17") (pin "P$1") (pinfunction "1_P$1") (pintype "passive"))
    )
    (net (code "44") (name "Net-(IC2-PA15{slash}XOUT{slash}EIC{slash}SCOM2PAD3+{slash}TC3)") (class "Default")
      (node (ref "IC2") (pin "24") (pinfunction "PA15/XOUT/EIC/SCOM2PAD3+/TC3_24") (pintype "bidirectional"))
      (node (ref "R4") (pin "1") (pinfunction "1_1") (pintype "passive"))
      (node (ref "U$2") (pin "P$2") (pinfunction "P$2_P$2") (pintype "bidirectional"))
    )
    (net (code "45") (name "Net-(IC2-PA18{slash}EIC{slash}SCOM1PAD2+{slash}TC3)") (class "Default")
      (node (ref "IC2") (pin "27") (pinfunction "PA18/EIC/SCOM1PAD2+/TC3_27") (pintype "bidirectional"))
      (node (ref "TP6") (pin "TP") (pinfunction "TP_TP") (pintype "input"))
    )
    (net (code "46") (name "Net-(IC2-PA19{slash}EIC{slash}SCOM1PAD3+{slash}TC3)") (class "Default")
      (node (ref "IC2") (pin "28") (pinfunction "PA19/EIC/SCOM1PAD3+/TC3_28") (pintype "bidirectional"))
      (node (ref "TP5") (pin "TP") (pinfunction "TP_TP") (pintype "input"))
    )
    (net (code "47") (name "Net-(IC2-PA20{slash}EIC{slash}SCOM5PAD2+)") (class "Default")
      (node (ref "IC2") (pin "29") (pinfunction "PA20/EIC/SCOM5PAD2+_29") (pintype "bidirectional"))
      (node (ref "TP10") (pin "TP") (pinfunction "TP_TP") (pintype "input"))
    )
    (net (code "48") (name "Net-(IC2-VDDANA)") (class "Default")
      (node (ref "C106") (pin "1") (pinfunction "1_1") (pintype "passive"))
      (node (ref "C107") (pin "1") (pinfunction "1_1") (pintype "passive"))
      (node (ref "IC2") (pin "6") (pinfunction "VDDANA_6") (pintype "power_in"))
      (node (ref "L100") (pin "1") (pinfunction "1_1") (pintype "passive"))
    )
    (net (code "49") (name "Net-(LED2-PadA)") (class "Default")
      (node (ref "LED2") (pin "A") (pinfunction "A_A") (pintype "passive"))
      (node (ref "R108") (pin "2") (pinfunction "2_2") (pintype "passive"))
    )
    (net (code "50") (name "Net-(U$6-FB)") (class "Default")
      (node (ref "C48") (pin "2") (pinfunction "2_2") (pintype "passive"))
      (node (ref "R39") (pin "1") (pinfunction "1_1") (pintype "passive"))
      (node (ref "R40") (pin "2") (pinfunction "2_2") (pintype "passive"))
      (node (ref "U$6") (pin "2") (pinfunction "FB_2") (pintype "bidirectional"))
    )
    (net (code "51") (name "Net-(U$6-NR{slash}SS)") (class "Default")
      (node (ref "C45") (pin "1") (pinfunction "1_1") (pintype "passive"))
      (node (ref "U$6") (pin "6") (pinfunction "NR/SS_6") (pintype "bidirectional"))
    )
    (net (code "52") (name "Net-(U$13-FB)") (class "Default")
      (node (ref "R8") (pin "2") (pinfunction "2_2") (pintype "passive"))
      (node (ref "R9") (pin "1") (pinfunction "1_1") (pintype "passive"))
      (node (ref "U$13") (pin "2") (pinfunction "FB_2") (pintype "bidirectional"))
    )
    (net (code "53") (name "Net-(U$13-L)") (class "Default")
      (node (ref "U$13") (pin "5") (pinfunction "L_5") (pintype "bidirectional"))
      (node (ref "U$16") (pin "P$2") (pinfunction "2_P$2") (pintype "passive"))
    )
    (net (code "54") (name "Net-(U$14-TRIM{slash}NR)") (class "Default")
      (node (ref "C4") (pin "2") (pinfunction "2_2") (pintype "passive"))
      (node (ref "U$14") (pin "5") (pinfunction "TRIM/NR_5") (pintype "bidirectional"))
    )
    (net (code "55") (name "Net-(U$27-EN)") (class "Default")
      (node (ref "C74") (pin "2") (pinfunction "2_2") (pintype "passive"))
      (node (ref "R10") (pin "2") (pinfunction "2_2") (pintype "passive"))
      (node (ref "U$27") (pin "1") (pinfunction "IN_1") (pintype "bidirectional"))
      (node (ref "U$27") (pin "3") (pinfunction "EN_3") (pintype "bidirectional"))
    )
    (net (code "56") (name "Net-(U$27-FB)") (class "Default")
      (node (ref "C69") (pin "2") (pinfunction "2_2") (pintype "passive"))
      (node (ref "U$27") (pin "4") (pinfunction "FB_4") (pintype "bidirectional"))
    )
    (net (code "57") (name "Net-(U3-PROG)") (class "Default")
      (node (ref "R12") (pin "2") (pinfunction "2_2") (pintype "passive"))
      (node (ref "U3") (pin "5") (pinfunction "PROG_5") (pintype "input"))
    )
    (net (code "58") (name "Net-(U3-STAT)") (class "Default")
      (node (ref "CHG1") (pin "C") (pinfunction "C_C") (pintype "passive"))
      (node (ref "U3") (pin "1") (pinfunction "STAT_1") (pintype "output"))
    )
    (net (code "59") (name "VBAT") (class "Default")
      (node (ref "C1") (pin "1") (pinfunction "1_1") (pintype "passive"))
      (node (ref "JP6") (pin "2") (pinfunction "2_2") (pintype "passive"))
      (node (ref "U$15") (pin "P1") (pinfunction "P1_P1") (pintype "bidirectional"))
      (node (ref "U3") (pin "3") (pinfunction "VBAT_3") (pintype "power_in"))
    )
    (net (code "60") (name "VCC") (class "Default")
      (node (ref "C2") (pin "2") (pinfunction "2_2") (pintype "passive"))
      (node (ref "C44") (pin "1") (pinfunction "1_1") (pintype "passive"))
      (node (ref "C83") (pin "1") (pinfunction "1_1") (pintype "passive"))
      (node (ref "R8") (pin "1") (pinfunction "1_1") (pintype "passive"))
      (node (ref "TP37") (pin "TP") (pinfunction "TP_TP") (pintype "input"))
      (node (ref "U$13") (pin "4") (pinfunction "VOUT_4") (pintype "bidirectional"))
      (node (ref "U$14") (pin "2") (pinfunction "VIN_2") (pintype "bidirectional"))
      (node (ref "U$6") (pin "5") (pinfunction "EN_5") (pintype "bidirectional"))
      (node (ref "U$6") (pin "8") (pinfunction "IN_8") (pintype "bidirectional"))
    )
    (net (code "61") (name "VCCIO") (class "Default")
      (node (ref "C7") (pin "1") (pinfunction "1_1") (pintype "passive"))
      (node (ref "C8") (pin "1") (pinfunction "1_1") (pintype "passive"))
      (node (ref "JP5") (pin "1") (pinfunction "VCC_1") (pintype "bidirectional"))
      (node (ref "R1") (pin "2") (pinfunction "2_2") (pintype "passive"))
      (node (ref "R7") (pin "1") (pinfunction "1_1") (pintype "passive"))
      (node (ref "U3") (pin "4") (pinfunction "VIN_4") (pintype "power_in"))
    )
    (net (code "62") (name "VCC{slash}2") (class "Default")
      (node (ref "C3") (pin "2") (pinfunction "2_2") (pintype "passive"))
      (node (ref "SV3") (pin "7") (pinfunction "7_7") (pintype "passive"))
      (node (ref "U$14") (pin "6") (pinfunction "VOUT_6") (pintype "bidirectional"))
    )
    (net (code "63") (name "VIN") (class "Default")
      (node (ref "C61") (pin "1") (pinfunction "1_1") (pintype "passive"))
      (node (ref "D3") (pin "C") (pinfunction "C_C") (pintype "passive"))
      (node (ref "R1") (pin "1") (pinfunction "1_1") (pintype "passive"))
      (node (ref "R10") (pin "1") (pinfunction "1_1") (pintype "passive"))
      (node (ref "U$13") (pin "1") (pinfunction "VIN_1") (pintype "bidirectional"))
      (node (ref "U$16") (pin "P$1") (pinfunction "1_P$1") (pintype "passive"))
    )
    (net (code "64") (name "unconnected-(CON_JTAG1-Pad6)") (class "Default")
      (node (ref "CON_JTAG1") (pin "6") (pinfunction "6_6") (pintype "bidirectional"))
    )
    (net (code "65") (name "unconnected-(CON_JTAG1-Pad7)") (class "Default")
      (node (ref "CON_JTAG1") (pin "7") (pinfunction "7_7") (pintype "bidirectional"))
    )
    (net (code "66") (name "unconnected-(CON_JTAG1-Pad8)") (class "Default")
      (node (ref "CON_JTAG1") (pin "8") (pinfunction "8_8") (pintype "bidirectional"))
    )
    (net (code "67") (name "unconnected-(IC2-PA2{slash}EIC{slash}AIN0-Pad3)") (class "Default")
      (node (ref "IC2") (pin "3") (pinfunction "PA2/EIC/AIN0_3") (pintype "bidirectional"))
    )
    (net (code "68") (name "unconnected-(IC2-PA14{slash}XIN{slash}EIC{slash}SCOM2PAD2+{slash}TC3-Pad23)") (class "Default")
      (node (ref "IC2") (pin "23") (pinfunction "PA14/XIN/EIC/SCOM2PAD2+/TC3_23") (pintype "bidirectional"))
    )
    (net (code "69") (name "unconnected-(IC2-PA21{slash}EIC{slash}SCOM5PAD3+-Pad30)") (class "Default")
      (node (ref "IC2") (pin "30") (pinfunction "PA21/EIC/SCOM5PAD3+_30") (pintype "bidirectional"))
    )
    (net (code "70") (name "unconnected-(IC2-PA22{slash}I2C{slash}EIC{slash}SCOM5PAD0+{slash}TC4-Pad31)") (class "Default")
      (node (ref "IC2") (pin "31") (pinfunction "PA22/I2C/EIC/SCOM5PAD0+/TC4_31") (pintype "bidirectional"))
    )
    (net (code "71") (name "unconnected-(IC2-PA23{slash}I2C{slash}EIC{slash}SCOM5PAD1+{slash}TC4-Pad32)") (class "Default")
      (node (ref "IC2") (pin "32") (pinfunction "PA23/I2C/EIC/SCOM5PAD1+/TC4_32") (pintype "bidirectional"))
    )
    (net (code "72") (name "unconnected-(IC2-PB3{slash}EIC{slash}AIN11{slash}SCOM5PAD1-Pad48)") (class "Default")
      (node (ref "IC2") (pin "48") (pinfunction "PB3/EIC/AIN11/SCOM5PAD1_48") (pintype "bidirectional"))
    )
    (net (code "73") (name "unconnected-(IC2-PB9{slash}EIC{slash}AIN3{slash}SCOM4PAD1{slash}{slash}TC4-Pad8)") (class "Default")
      (node (ref "IC2") (pin "8") (pinfunction "PB9/EIC/AIN3/SCOM4PAD1//TC4_8") (pintype "bidirectional"))
    )
    (net (code "74") (name "unconnected-(TP2-PadTP)") (class "Default")
      (node (ref "TP2") (pin "TP") (pinfunction "TP_TP") (pintype "input"))
    )
    (net (code "75") (name "unconnected-(TP3-PadTP)") (class "Default")
      (node (ref "TP3") (pin "TP") (pinfunction "TP_TP") (pintype "input"))
    )
    (net (code "76") (name "unconnected-(TP4-PadTP)") (class "Default")
      (node (ref "TP4") (pin "TP") (pinfunction "TP_TP") (pintype "input"))
    )
    (net (code "77") (name "unconnected-(TP7-PadTP)") (class "Default")
      (node (ref "TP7") (pin "TP") (pinfunction "TP_TP") (pintype "input"))
    )
    (net (code "78") (name "unconnected-(TP8-PadTP)") (class "Default")
      (node (ref "TP8") (pin "TP") (pinfunction "TP_TP") (pintype "input"))
    )
    (net (code "79") (name "unconnected-(TP9-PadTP)") (class "Default")
      (node (ref "TP9") (pin "TP") (pinfunction "TP_TP") (pintype "input"))
    )
    (net (code "80") (name "unconnected-(TP11-PadTP)") (class "Default")
      (node (ref "TP11") (pin "TP") (pinfunction "TP_TP") (pintype "input"))
    )
    (net (code "81") (name "unconnected-(TP12-PadTP)") (class "Default")
      (node (ref "TP12") (pin "TP") (pinfunction "TP_TP") (pintype "input"))
    )
    (net (code "82") (name "unconnected-(TP13-PadTP)") (class "Default")
      (node (ref "TP13") (pin "TP") (pinfunction "TP_TP") (pintype "input"))
    )
    (net (code "83") (name "unconnected-(TP14-PadTP)") (class "Default")
      (node (ref "TP14") (pin "TP") (pinfunction "TP_TP") (pintype "input"))
    )
    (net (code "84") (name "unconnected-(TP15-PadTP)") (class "Default")
      (node (ref "TP15") (pin "TP") (pinfunction "TP_TP") (pintype "input"))
    )
    (net (code "85") (name "unconnected-(TP16-PadTP)") (class "Default")
      (node (ref "TP16") (pin "TP") (pinfunction "TP_TP") (pintype "input"))
    )
    (net (code "86") (name "unconnected-(TP17-PadTP)") (class "Default")
      (node (ref "TP17") (pin "TP") (pinfunction "TP_TP") (pintype "input"))
    )
    (net (code "87") (name "unconnected-(TP18-PadTP)") (class "Default")
      (node (ref "TP18") (pin "TP") (pinfunction "TP_TP") (pintype "input"))
    )
    (net (code "88") (name "unconnected-(TP19-PadTP)") (class "Default")
      (node (ref "TP19") (pin "TP") (pinfunction "TP_TP") (pintype "input"))
    )
    (net (code "89") (name "unconnected-(TP20-PadTP)") (class "Default")
      (node (ref "TP20") (pin "TP") (pinfunction "TP_TP") (pintype "input"))
    )
    (net (code "90") (name "unconnected-(TP21-PadTP)") (class "Default")
      (node (ref "TP21") (pin "TP") (pinfunction "TP_TP") (pintype "input"))
    )
    (net (code "91") (name "unconnected-(TP22-PadTP)") (class "Default")
      (node (ref "TP22") (pin "TP") (pinfunction "TP_TP") (pintype "input"))
    )
    (net (code "92") (name "unconnected-(TP23-PadTP)") (class "Default")
      (node (ref "TP23") (pin "TP") (pinfunction "TP_TP") (pintype "input"))
    )
    (net (code "93") (name "unconnected-(TP24-PadTP)") (class "Default")
      (node (ref "TP24") (pin "TP") (pinfunction "TP_TP") (pintype "input"))
    )
    (net (code "94") (name "unconnected-(TP25-PadTP)") (class "Default")
      (node (ref "TP25") (pin "TP") (pinfunction "TP_TP") (pintype "input"))
    )
    (net (code "95") (name "unconnected-(TP26-PadTP)") (class "Default")
      (node (ref "TP26") (pin "TP") (pinfunction "TP_TP") (pintype "input"))
    )
    (net (code "96") (name "unconnected-(TP27-PadTP)") (class "Default")
      (node (ref "TP27") (pin "TP") (pinfunction "TP_TP") (pintype "input"))
    )
    (net (code "97") (name "unconnected-(TP28-PadTP)") (class "Default")
      (node (ref "TP28") (pin "TP") (pinfunction "TP_TP") (pintype "input"))
    )
    (net (code "98") (name "unconnected-(TP29-PadTP)") (class "Default")
      (node (ref "TP29") (pin "TP") (pinfunction "TP_TP") (pintype "input"))
    )
    (net (code "99") (name "unconnected-(TP30-PadTP)") (class "Default")
      (node (ref "TP30") (pin "TP") (pinfunction "TP_TP") (pintype "input"))
    )
    (net (code "100") (name "unconnected-(TP31-PadTP)") (class "Default")
      (node (ref "TP31") (pin "TP") (pinfunction "TP_TP") (pintype "input"))
    )
    (net (code "101") (name "unconnected-(TP32-PadTP)") (class "Default")
      (node (ref "TP32") (pin "TP") (pinfunction "TP_TP") (pintype "input"))
    )
    (net (code "102") (name "unconnected-(TP33-PadTP)") (class "Default")
      (node (ref "TP33") (pin "TP") (pinfunction "TP_TP") (pintype "input"))
    )
    (net (code "103") (name "unconnected-(TP34-PadTP)") (class "Default")
      (node (ref "TP34") (pin "TP") (pinfunction "TP_TP") (pintype "input"))
    )
    (net (code "104") (name "unconnected-(TP35-PadTP)") (class "Default")
      (node (ref "TP35") (pin "TP") (pinfunction "TP_TP") (pintype "input"))
    )
    (net (code "105") (name "unconnected-(TP38-PadTP)") (class "Default")
      (node (ref "TP38") (pin "TP") (pinfunction "TP_TP") (pintype "input"))
    )
    (net (code "106") (name "unconnected-(TP39-PadTP)") (class "Default")
      (node (ref "TP39") (pin "TP") (pinfunction "TP_TP") (pintype "input"))
    )
    (net (code "107") (name "unconnected-(TP40-PadTP)") (class "Default")
      (node (ref "TP40") (pin "TP") (pinfunction "TP_TP") (pintype "input"))
    )
    (net (code "108") (name "unconnected-(TP42-PadTP)") (class "Default")
      (node (ref "TP42") (pin "TP") (pinfunction "TP_TP") (pintype "input"))
    )
    (net (code "109") (name "unconnected-(TP43-PadTP)") (class "Default")
      (node (ref "TP43") (pin "TP") (pinfunction "TP_TP") (pintype "input"))
    )
    (net (code "110") (name "unconnected-(TP46-PadTP)") (class "Default")
      (node (ref "TP46") (pin "TP") (pinfunction "TP_TP") (pintype "input"))
    )
    (net (code "111") (name "unconnected-(TP47-PadTP)") (class "Default")
      (node (ref "TP47") (pin "TP") (pinfunction "TP_TP") (pintype "input"))
    )
    (net (code "112") (name "unconnected-(TP48-PadTP)") (class "Default")
      (node (ref "TP48") (pin "TP") (pinfunction "TP_TP") (pintype "input"))
    )
    (net (code "113") (name "unconnected-(TP50-PadTP)") (class "Default")
      (node (ref "TP50") (pin "TP") (pinfunction "TP_TP") (pintype "input"))
    )
    (net (code "114") (name "unconnected-(TP51-PadTP)") (class "Default")
      (node (ref "TP51") (pin "TP") (pinfunction "TP_TP") (pintype "input"))
    )
    (net (code "115") (name "unconnected-(TP53-PadTP)") (class "Default")
      (node (ref "TP53") (pin "TP") (pinfunction "TP_TP") (pintype "input"))
    )
    (net (code "116") (name "unconnected-(TP54-PadTP)") (class "Default")
      (node (ref "TP54") (pin "TP") (pinfunction "TP_TP") (pintype "input"))
    )
    (net (code "117") (name "unconnected-(TP55-PadTP)") (class "Default")
      (node (ref "TP55") (pin "TP") (pinfunction "TP_TP") (pintype "input"))
    )
    (net (code "118") (name "unconnected-(TP58-PadTP)") (class "Default")
      (node (ref "TP58") (pin "TP") (pinfunction "TP_TP") (pintype "input"))
    )
    (net (code "119") (name "unconnected-(TP59-PadTP)") (class "Default")
      (node (ref "TP59") (pin "TP") (pinfunction "TP_TP") (pintype "input"))
    )
    (net (code "120") (name "unconnected-(TP60-PadTP)") (class "Default")
      (node (ref "TP60") (pin "TP") (pinfunction "TP_TP") (pintype "input"))
    )
    (net (code "121") (name "unconnected-(TP62-PadTP)") (class "Default")
      (node (ref "TP62") (pin "TP") (pinfunction "TP_TP") (pintype "input"))
    )
    (net (code "122") (name "unconnected-(TP63-PadTP)") (class "Default")
      (node (ref "TP63") (pin "TP") (pinfunction "TP_TP") (pintype "input"))
    )
    (net (code "123") (name "unconnected-(TP65-PadTP)") (class "Default")
      (node (ref "TP65") (pin "TP") (pinfunction "TP_TP") (pintype "input"))
    )
    (net (code "124") (name "unconnected-(TP66-PadTP)") (class "Default")
      (node (ref "TP66") (pin "TP") (pinfunction "TP_TP") (pintype "input"))
    )
    (net (code "125") (name "unconnected-(TP68-PadTP)") (class "Default")
      (node (ref "TP68") (pin "TP") (pinfunction "TP_TP") (pintype "input"))
    )
    (net (code "126") (name "unconnected-(TP69-PadTP)") (class "Default")
      (node (ref "TP69") (pin "TP") (pinfunction "TP_TP") (pintype "input"))
    )
    (net (code "127") (name "unconnected-(TP70-PadTP)") (class "Default")
      (node (ref "TP70") (pin "TP") (pinfunction "TP_TP") (pintype "input"))
    )
    (net (code "128") (name "unconnected-(TP71-PadTP)") (class "Default")
      (node (ref "TP71") (pin "TP") (pinfunction "TP_TP") (pintype "input"))
    )
    (net (code "129") (name "unconnected-(TP72-PadTP)") (class "Default")
      (node (ref "TP72") (pin "TP") (pinfunction "TP_TP") (pintype "input"))
    )
    (net (code "130") (name "unconnected-(TP73-PadTP)") (class "Default")
      (node (ref "TP73") (pin "TP") (pinfunction "TP_TP") (pintype "input"))
    )
    (net (code "131") (name "unconnected-(TP74-PadTP)") (class "Default")
      (node (ref "TP74") (pin "TP") (pinfunction "TP_TP") (pintype "input"))
    )
    (net (code "132") (name "unconnected-(U$14-TEMP-Pad3)") (class "Default")
      (node (ref "U$14") (pin "3") (pinfunction "TEMP_3") (pintype "bidirectional"))
    )
    (net (code "133") (name "unconnected-(U$15-PadP3)") (class "Default")
      (node (ref "U$15") (pin "P3") (pinfunction "P3_P3") (pintype "bidirectional"))
    )
  )
)
